# SD.net
KiCad netlist of a schematic drawn in Altium Designer
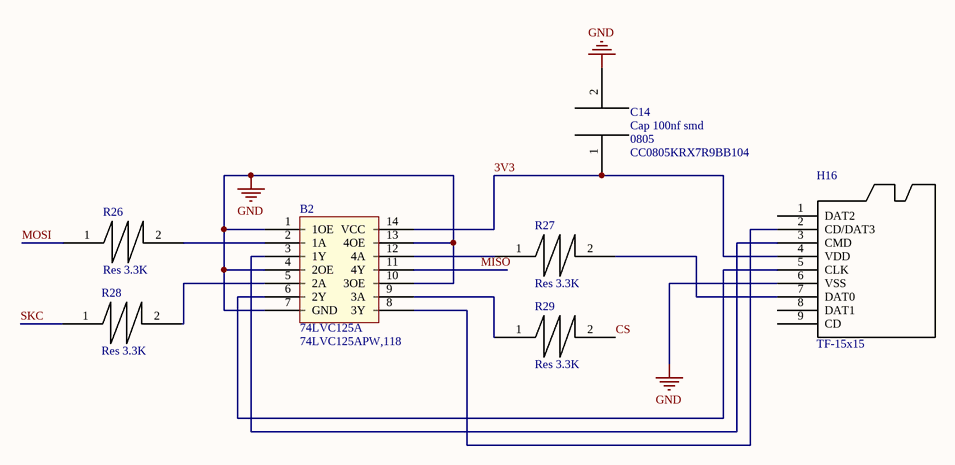
[diagram p0: SD.SchDoc]

(export (version "E")
  (design (tool "Eeschema 10.0.6"))
  (components
    (comp (ref "B2")
      (value "74LVC125A")
      (footprint "74LVC125APW,118")
      (fields (field (name "MFR.PART #") "74LVC125APW,118"))
      (libsource (lib "Integrated_Library") (part "74LVC125A"))
    )
    (comp (ref "C14")
      (value "Cap 100nf smd")
      (footprint "CAP100NFSMD")
      (description "100nf")
      (fields (field (name "PACKAGE") "0805") (field (name "MFR.PART #") "CC0805KRX7R9BB104"))
      (libsource (lib "Integrated_Library") (part "Cap 100nf smd"))
    )
    (comp (ref "H16")
      (value "TF-15x15")
      (footprint "TF-15x15")
      (libsource (lib "Integrated_Library") (part "TF-15x15"))
    )
    (comp (ref "R26")
      (value "Res 3.3K")
      (footprint "Res 3.3K")
      (description "AECR0805F3K30K9")
      (libsource (lib "Integrated_Library") (part "Res 3.3K"))
    )
    (comp (ref "R27")
      (value "Res 3.3K")
      (footprint "Res 3.3K")
      (description "AECR0805F3K30K9")
      (libsource (lib "Integrated_Library") (part "Res 3.3K"))
    )
    (comp (ref "R28")
      (value "Res 3.3K")
      (footprint "Res 3.3K")
      (description "AECR0805F3K30K9")
      (libsource (lib "Integrated_Library") (part "Res 3.3K"))
    )
    (comp (ref "R29")
      (value "Res 3.3K")
      (footprint "Res 3.3K")
      (description "AECR0805F3K30K9")
      (libsource (lib "Integrated_Library") (part "Res 3.3K"))
    )
  )
  (nets
    (net (code "1") (name "/3V3") (class "Default")
      (node (ref "B2") (pin "14") (pinfunction "VCC_14") (pintype "passive"))
      (node (ref "C14") (pin "1") (pinfunction "1_1") (pintype "passive"))
      (node (ref "H16") (pin "4") (pinfunction "VDD_4") (pintype "passive"))
    )
    (net (code "2") (name "/CS") (class "Default")
      (node (ref "R29") (pin "2") (pinfunction "2_2") (pintype "passive"))
    )
    (net (code "3") (name "/MISO") (class "Default")
      (node (ref "B2") (pin "11") (pinfunction "4Y_11") (pintype "passive"))
    )
    (net (code "4") (name "/MOSI") (class "Default")
      (node (ref "R26") (pin "1") (pinfunction "1_1") (pintype "passive"))
    )
    (net (code "5") (name "/SKC") (class "Default")
      (node (ref "R28") (pin "1") (pinfunction "1_1") (pintype "passive"))
    )
    (net (code "6") (name "GND") (class "Default")
      (node (ref "B2") (pin "1") (pinfunction "1OE_1") (pintype "passive"))
      (node (ref "B2") (pin "10") (pinfunction "3OE_10") (pintype "passive"))
      (node (ref "B2") (pin "13") (pinfunction "4OE_13") (pintype "passive"))
      (node (ref "B2") (pin "4") (pinfunction "2OE_4") (pintype "passive"))
      (node (ref "B2") (pin "7") (pinfunction "GND_7") (pintype "passive"))
      (node (ref "C14") (pin "2") (pinfunction "2_2") (pintype "passive"))
      (node (ref "H16") (pin "6") (pinfunction "VSS_6") (pintype "passive"))
    )
    (net (code "7") (name "Net-(B2-1A)") (class "Default")
      (node (ref "B2") (pin "2") (pinfunction "1A_2") (pintype "passive"))
      (node (ref "R26") (pin "2") (pinfunction "2_2") (pintype "passive"))
    )
    (net (code "8") (name "Net-(B2-1Y)") (class "Default")
      (node (ref "B2") (pin "3") (pinfunction "1Y_3") (pintype "passive"))
      (node (ref "H16") (pin "3") (pinfunction "CMD_3") (pintype "passive"))
    )
    (net (code "9") (name "Net-(B2-2A)") (class "Default")
      (node (ref "B2") (pin "5") (pinfunction "2A_5") (pintype "passive"))
      (node (ref "R28") (pin "2") (pinfunction "2_2") (pintype "passive"))
    )
    (net (code "10") (name "Net-(B2-2Y)") (class "Default")
      (node (ref "B2") (pin "6") (pinfunction "2Y_6") (pintype "passive"))
      (node (ref "H16") (pin "5") (pinfunction "CLK_5") (pintype "passive"))
    )
    (net (code "11") (name "Net-(B2-3A)") (class "Default")
      (node (ref "B2") (pin "9") (pinfunction "3A_9") (pintype "passive"))
      (node (ref "R29") (pin "1") (pinfunction "1_1") (pintype "passive"))
    )
    (net (code "12") (name "Net-(B2-3Y)") (class "Default")
      (node (ref "B2") (pin "8") (pinfunction "3Y_8") (pintype "passive"))
      (node (ref "H16") (pin "2") (pinfunction "CD/DAT3_2") (pintype "passive"))
    )
    (net (code "13") (name "Net-(B2-4A)") (class "Default")
      (node (ref "B2") (pin "12") (pinfunction "4A_12") (pintype "passive"))
      (node (ref "R27") (pin "1") (pinfunction "1_1") (pintype "passive"))
    )
    (net (code "14") (name "Net-(H16-DAT0)") (class "Default")
      (node (ref "H16") (pin "7") (pinfunction "DAT0_7") (pintype "passive"))
      (node (ref "R27") (pin "2") (pinfunction "2_2") (pintype "passive"))
    )
    (net (code "15") (name "unconnected-(H16-CD-Pad9)") (class "Default")
      (node (ref "H16") (pin "9") (pinfunction "CD_9") (pintype "passive"))
    )
    (net (code "16") (name "unconnected-(H16-DAT1-Pad8)") (class "Default")
      (node (ref "H16") (pin "8") (pinfunction "DAT1_8") (pintype "passive"))
    )
    (net (code "17") (name "unconnected-(H16-DAT2-Pad1)") (class "Default")
      (node (ref "H16") (pin "1") (pinfunction "DAT2_1") (pintype "passive"))
    )
  )
)
